# plp-ctop_2d.net
KiCad netlist of a schematic drawn in Altium Designer
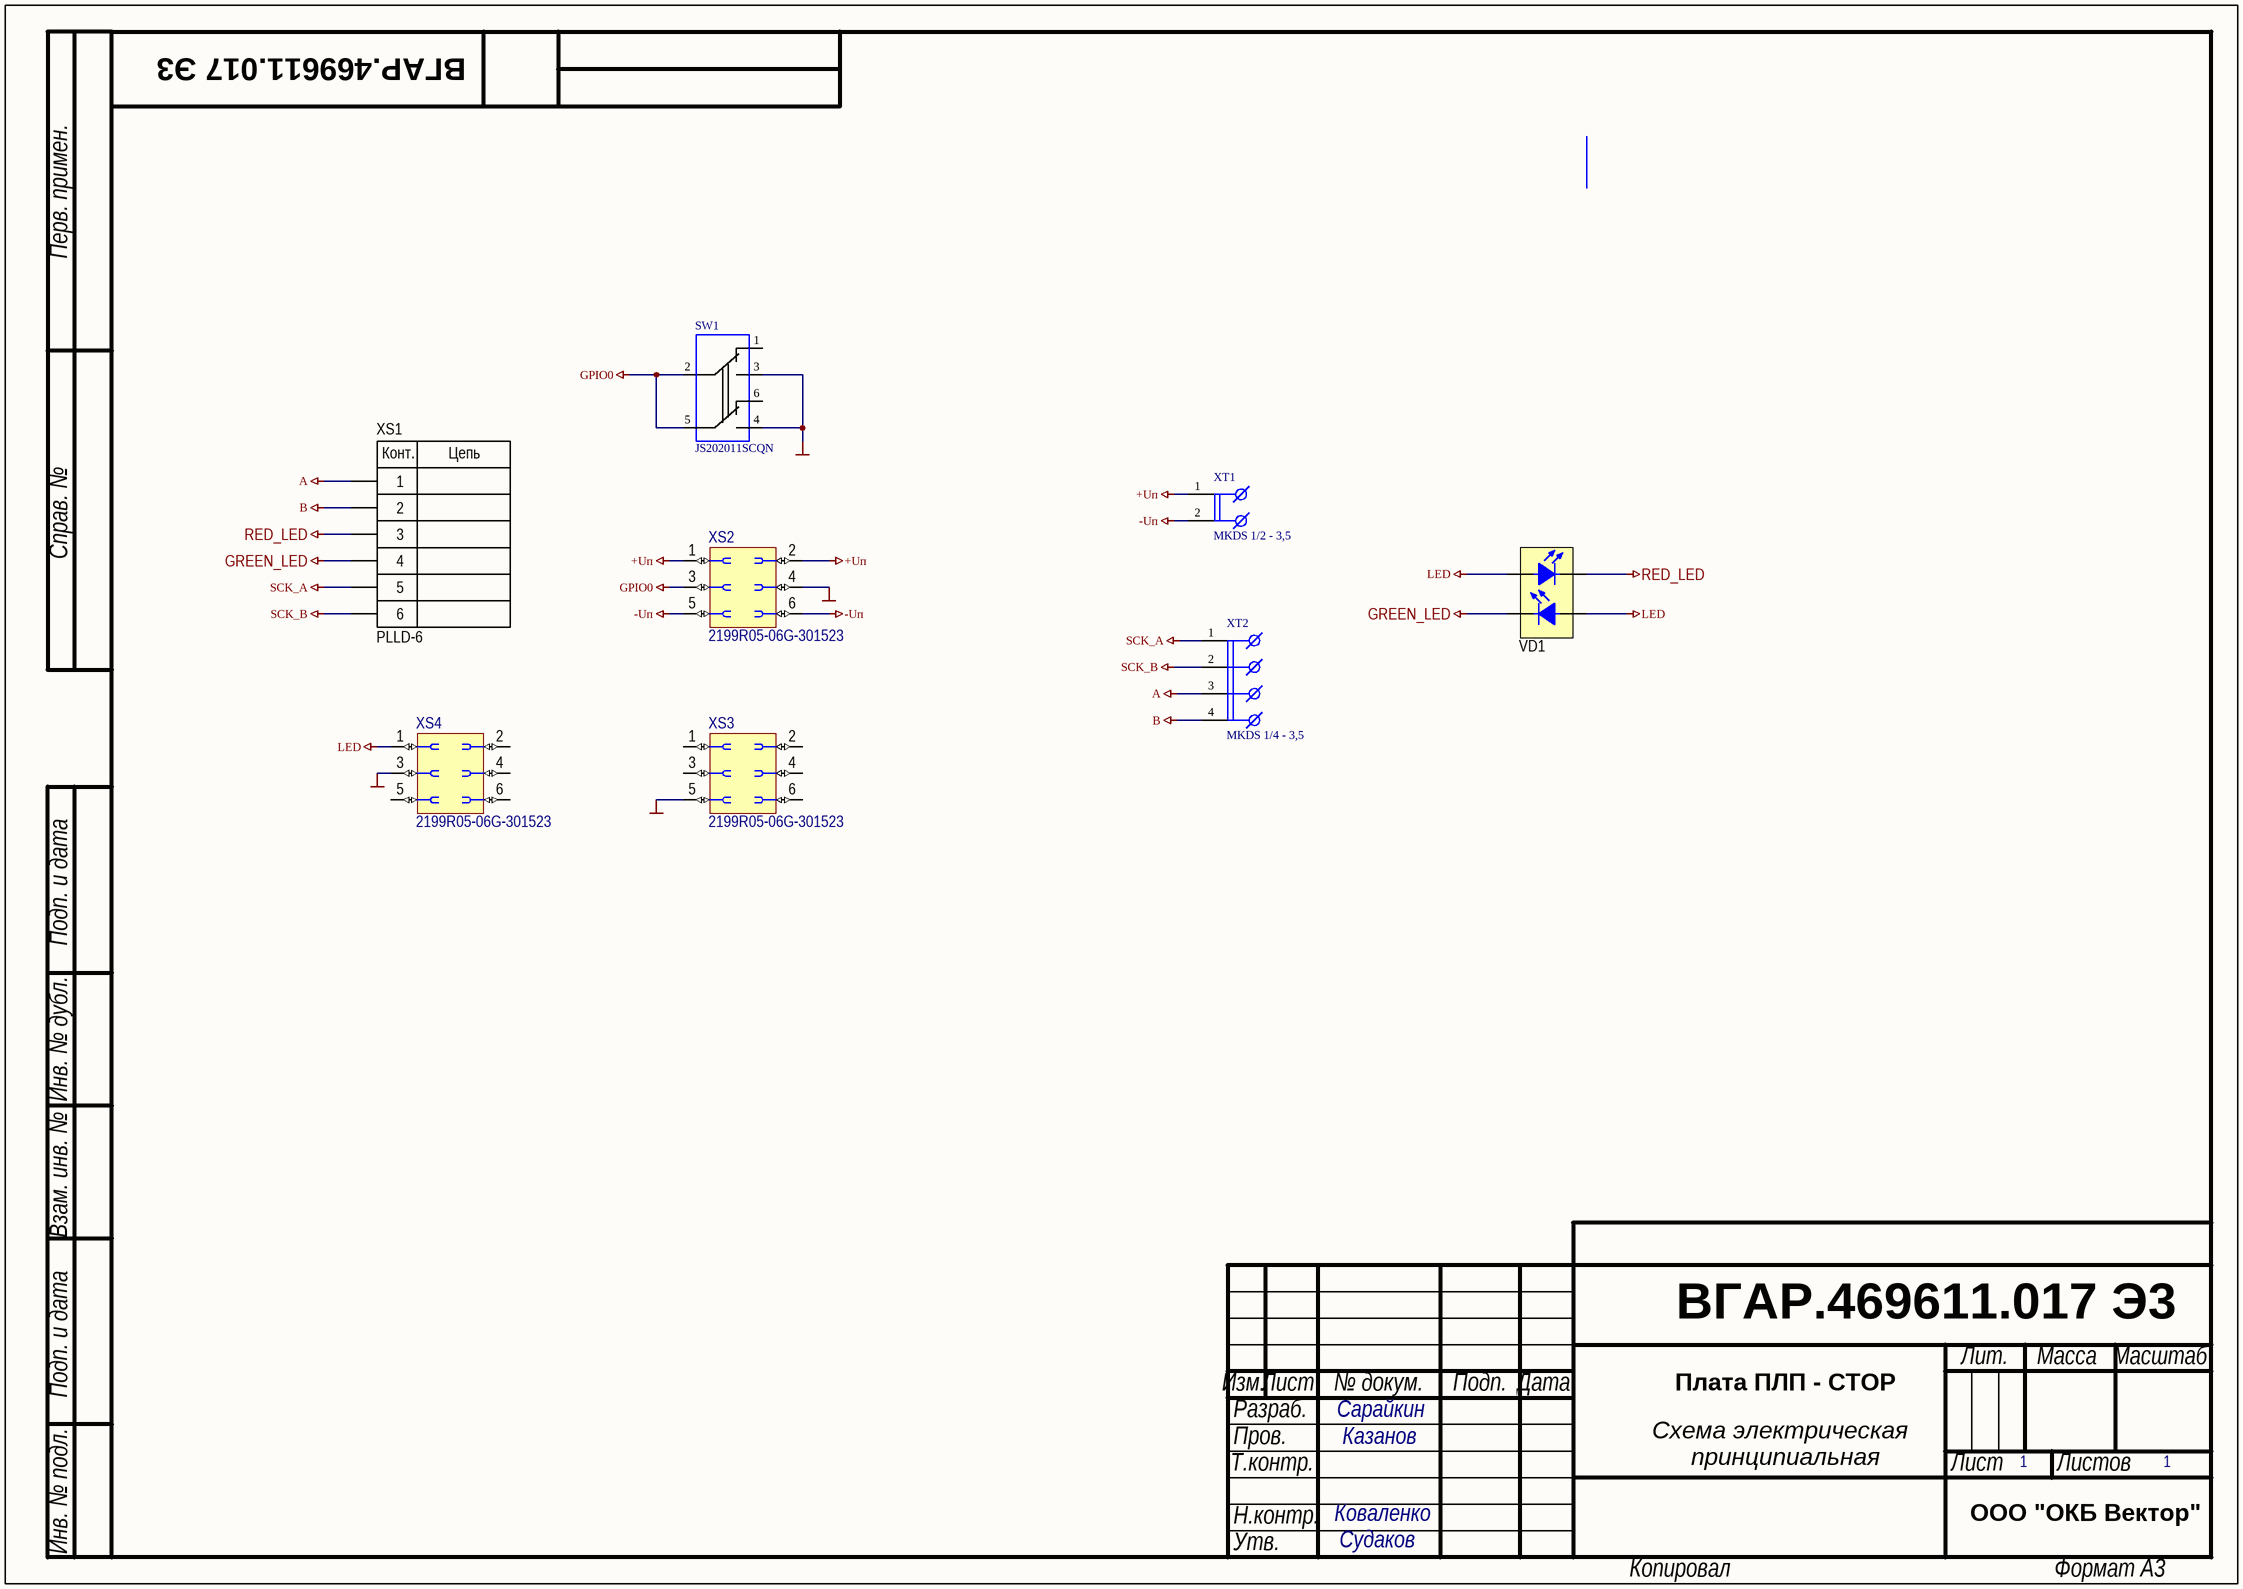
[diagram p0: plp-ctop_2d.SchDoc]

(export (version "E")
  (design (tool "Eeschema 10.0.6"))
  (components
    (comp (ref "SW1")
      (value "JS202011SCQN")
      (footprint "JS202011SCQN")
      (description "Переключатель")
      (fields
        (field (name "MANUFACTURER") "C&K Component")
        (field (name "REPLACEMENTPART1PARTNUMBER") "is-1390")
      )
      (libsource (lib "Switch") (part "JS202011SCQN"))
    )
    (comp (ref "VD1")
      (value "Dual LED")
      (footprint "KAA-3528")
      (description "2-1 RED, 4-3 GREEN")
      (libsource (lib "diode") (part "Dual LED"))
    )
    (comp (ref "XS1")
      (value "PLLD-6")
      (footprint "CON: PLL-6(2x3R1.27female)")
      (description "Step 1.27")
      (libsource (lib "connector") (part "PLLD-6(Female)"))
    )
    (comp (ref "XS2")
      (value "2199R05-06G-301523")
      (footprint "CON: PLL-6(2x3R1.27female)")
      (description "Step 1.27")
      (libsource (lib "connector") (part "2199R05-06G-301523In"))
    )
    (comp (ref "XS3")
      (value "2199R05-06G-301523")
      (footprint "CON: PLL-6(2x3R1.27female)")
      (description "Step 1.27")
      (libsource (lib "connector") (part "2199R05-06G-301523In"))
    )
    (comp (ref "XS4")
      (value "2199R05-06G-301523")
      (footprint "CON: PLL-6(2x3R1.27female)")
      (description "Step 1.27")
      (libsource (lib "connector") (part "2199R05-06G-301523In"))
    )
    (comp (ref "XT1")
      (value "MKDS 1/2 - 3,5")
      (footprint "MKDS 1/2 - 3,5")
      (libsource (lib "Phoenixcontact Terminal Block") (part "MKDS 1/2 - 3,5"))
    )
    (comp (ref "XT2")
      (value "MKDS 1/4 - 3,5")
      (footprint "MKDS 1/4 - 3,5")
      (libsource (lib "Phoenixcontact Terminal Block") (part "MKDS 1/4 - 3,5"))
    )
  )
  (nets
    (net (code "1") (name "+Uп") (class "Default")
      (node (ref "XS2") (pin "1") (pinfunction "1_1") (pintype "bidirectional"))
      (node (ref "XS2") (pin "2") (pinfunction "2_2") (pintype "bidirectional"))
      (node (ref "XT1") (pin "1") (pintype "passive"))
    )
    (net (code "2") (name "-Uп") (class "Default")
      (node (ref "XS2") (pin "5") (pinfunction "5_5") (pintype "bidirectional"))
      (node (ref "XS2") (pin "6") (pinfunction "6_6") (pintype "bidirectional"))
      (node (ref "XT1") (pin "2") (pintype "passive"))
    )
    (net (code "3") (name "A") (class "Default")
      (node (ref "XS1") (pin "1") (pinfunction "1_1") (pintype "passive"))
      (node (ref "XT2") (pin "3") (pintype "passive"))
    )
    (net (code "4") (name "B") (class "Default")
      (node (ref "XS1") (pin "2") (pinfunction "2_2") (pintype "passive"))
      (node (ref "XT2") (pin "4") (pinfunction "4_4") (pintype "passive"))
    )
    (net (code "5") (name "GND") (class "Default")
      (node (ref "SW1") (pin "3") (pinfunction "3_3") (pintype "passive"))
      (node (ref "SW1") (pin "4") (pinfunction "4_4") (pintype "passive"))
      (node (ref "XS2") (pin "4") (pinfunction "4_4") (pintype "bidirectional"))
      (node (ref "XS3") (pin "5") (pinfunction "5_5") (pintype "bidirectional"))
      (node (ref "XS4") (pin "3") (pinfunction "3_3") (pintype "bidirectional"))
    )
    (net (code "6") (name "GPIO0") (class "Default")
      (node (ref "SW1") (pin "2") (pinfunction "2_2") (pintype "passive"))
      (node (ref "SW1") (pin "5") (pinfunction "5_5") (pintype "passive"))
      (node (ref "XS2") (pin "3") (pinfunction "3_3") (pintype "bidirectional"))
    )
    (net (code "7") (name "GREEN_LED") (class "Default")
      (node (ref "VD1") (pin "3") (pinfunction "C_3") (pintype "passive"))
      (node (ref "XS1") (pin "4") (pinfunction "4_4") (pintype "passive"))
    )
    (net (code "8") (name "LED") (class "Default")
      (node (ref "VD1") (pin "2") (pinfunction "A_2") (pintype "passive"))
      (node (ref "VD1") (pin "4") (pinfunction "A_4") (pintype "passive"))
      (node (ref "XS4") (pin "1") (pinfunction "1_1") (pintype "bidirectional"))
    )
    (net (code "9") (name "RED_LED") (class "Default")
      (node (ref "VD1") (pin "1") (pinfunction "C_1") (pintype "passive"))
      (node (ref "XS1") (pin "3") (pinfunction "3_3") (pintype "passive"))
    )
    (net (code "10") (name "SCK_A") (class "Default")
      (node (ref "XS1") (pin "5") (pinfunction "5_5") (pintype "passive"))
      (node (ref "XT2") (pin "1") (pintype "passive"))
    )
    (net (code "11") (name "SCK_B") (class "Default")
      (node (ref "XS1") (pin "6") (pinfunction "6_6") (pintype "passive"))
      (node (ref "XT2") (pin "2") (pintype "passive"))
    )
    (net (code "12") (name "unconnected-(SW1-Pad1)") (class "Default")
      (node (ref "SW1") (pin "1") (pinfunction "1_1") (pintype "passive"))
    )
    (net (code "13") (name "unconnected-(SW1-Pad6)") (class "Default")
      (node (ref "SW1") (pin "6") (pinfunction "6_6") (pintype "passive"))
    )
    (net (code "14") (name "unconnected-(XS3-Pad1)") (class "Default")
      (node (ref "XS3") (pin "1") (pinfunction "1_1") (pintype "bidirectional"))
    )
    (net (code "15") (name "unconnected-(XS3-Pad2)") (class "Default")
      (node (ref "XS3") (pin "2") (pinfunction "2_2") (pintype "bidirectional"))
    )
    (net (code "16") (name "unconnected-(XS3-Pad3)") (class "Default")
      (node (ref "XS3") (pin "3") (pinfunction "3_3") (pintype "bidirectional"))
    )
    (net (code "17") (name "unconnected-(XS3-Pad4)") (class "Default")
      (node (ref "XS3") (pin "4") (pinfunction "4_4") (pintype "bidirectional"))
    )
    (net (code "18") (name "unconnected-(XS3-Pad6)") (class "Default")
      (node (ref "XS3") (pin "6") (pinfunction "6_6") (pintype "bidirectional"))
    )
    (net (code "19") (name "unconnected-(XS4-Pad2)") (class "Default")
      (node (ref "XS4") (pin "2") (pinfunction "2_2") (pintype "bidirectional"))
    )
    (net (code "20") (name "unconnected-(XS4-Pad4)") (class "Default")
      (node (ref "XS4") (pin "4") (pinfunction "4_4") (pintype "bidirectional"))
    )
    (net (code "21") (name "unconnected-(XS4-Pad5)") (class "Default")
      (node (ref "XS4") (pin "5") (pinfunction "5_5") (pintype "bidirectional"))
    )
    (net (code "22") (name "unconnected-(XS4-Pad6)") (class "Default")
      (node (ref "XS4") (pin "6") (pinfunction "6_6") (pintype "bidirectional"))
    )
  )
)
